# peripheral.net
KiCad netlist of a schematic drawn in Altium Designer
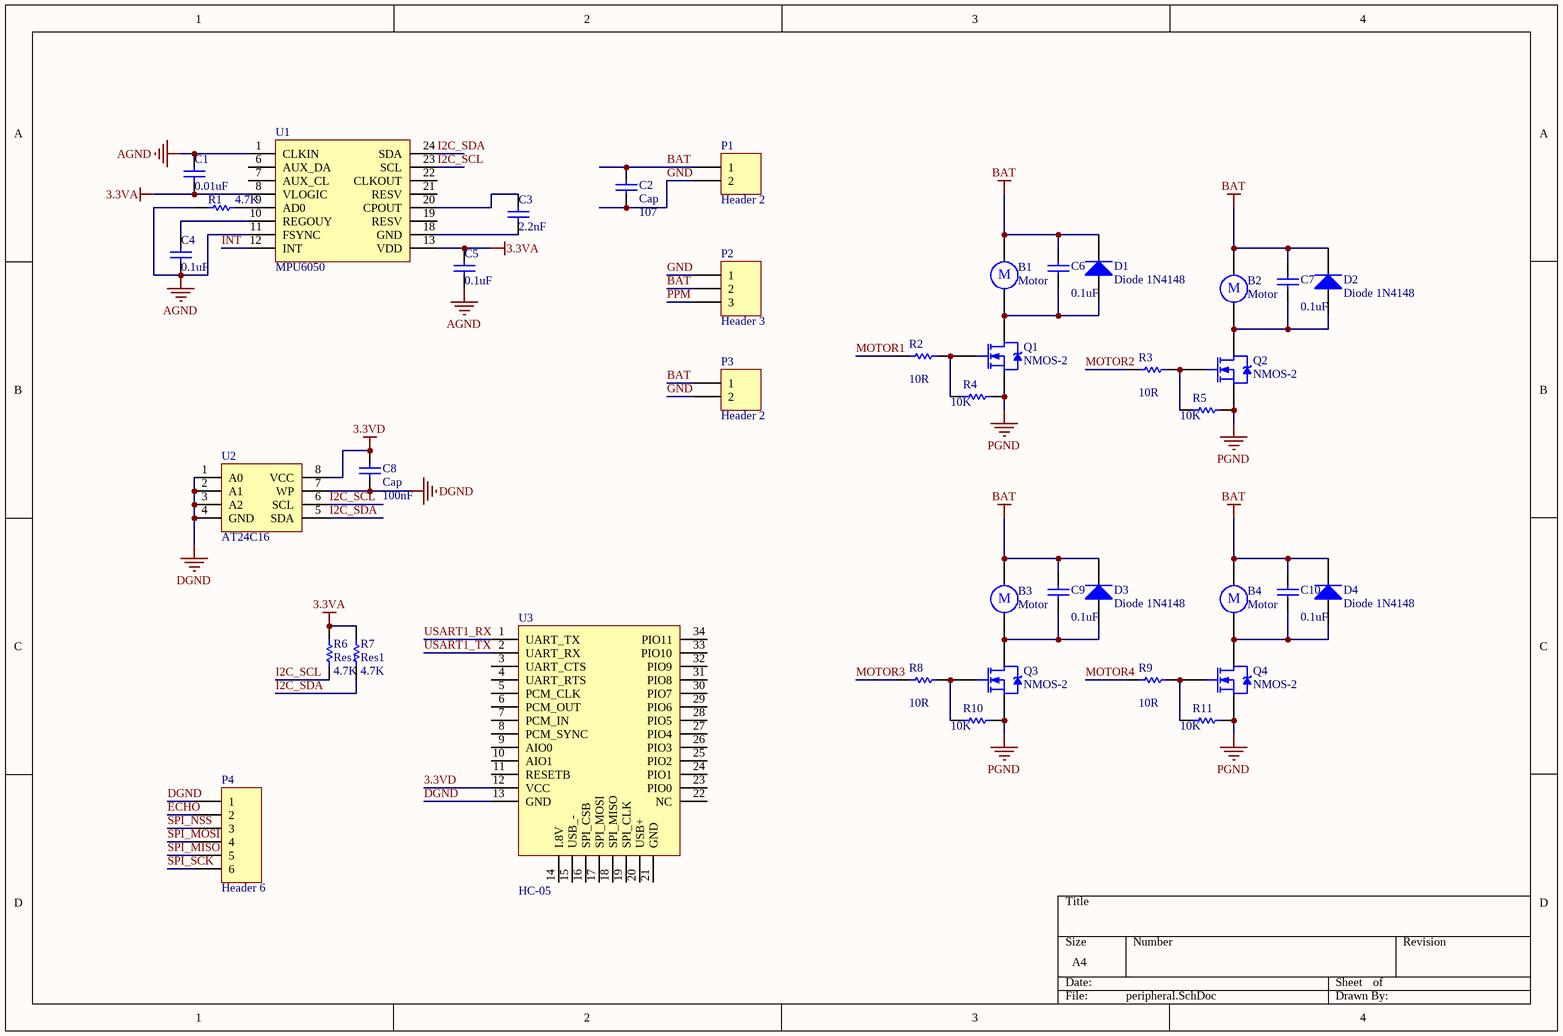
[diagram p0: peripheral.SchDoc]

(export (version "E")
  (design (tool "Eeschema 10.0.6"))
  (components
    (comp (ref "B1")
      (value "Motor")
      (footprint "HDR1X2")
      (description "Motor, General Kind")
      (fields (field (name "PUBLISHER") "Altium Limited"))
      (libsource (lib "Miscellaneous Devices") (part "Motor"))
    )
    (comp (ref "B2")
      (value "Motor")
      (footprint "HDR1X2")
      (description "Motor, General Kind")
      (fields (field (name "PUBLISHER") "Altium Limited"))
      (libsource (lib "Miscellaneous Devices") (part "Motor"))
    )
    (comp (ref "B3")
      (value "Motor")
      (footprint "HDR1X2")
      (description "Motor, General Kind")
      (fields (field (name "PUBLISHER") "Altium Limited"))
      (libsource (lib "Miscellaneous Devices") (part "Motor"))
    )
    (comp (ref "B4")
      (value "Motor")
      (footprint "HDR1X2")
      (description "Motor, General Kind")
      (fields (field (name "PUBLISHER") "Altium Limited"))
      (libsource (lib "Miscellaneous Devices") (part "Motor"))
    )
    (comp (ref "C1")
      (value "0.01uF")
      (footprint "C0402")
      (description "Capacitor")
      (fields (field (name "Comment") "Cap") (field (name "PUBLISHER") "Altium Limited"))
      (libsource (lib "Miscellaneous Devices") (part "Cap"))
    )
    (comp (ref "C2")
      (value "Cap")
      (footprint "1206R")
      (description "Capacitor")
      (fields (field (name "ALTIUM_VALUE") "107") (field (name "PUBLISHER") "Altium Limited"))
      (libsource (lib "Miscellaneous Devices") (part "Cap"))
    )
    (comp (ref "C3")
      (value "2.2nF")
      (footprint "C0402")
      (description "Capacitor")
      (fields (field (name "Comment") "Cap") (field (name "PUBLISHER") "Altium Limited"))
      (libsource (lib "Miscellaneous Devices") (part "Cap"))
    )
    (comp (ref "C4")
      (value "0.1uF")
      (footprint "C0402")
      (description "Capacitor")
      (fields (field (name "Comment") "Cap") (field (name "PUBLISHER") "Altium Limited"))
      (libsource (lib "Miscellaneous Devices") (part "Cap"))
    )
    (comp (ref "C5")
      (value "0.1uF")
      (footprint "C0402")
      (description "Capacitor")
      (fields (field (name "Comment") "Cap") (field (name "PUBLISHER") "Altium Limited"))
      (libsource (lib "Miscellaneous Devices") (part "Cap"))
    )
    (comp (ref "C6")
      (value "0.1uF")
      (footprint "c0603")
      (description "Capacitor")
      (fields (field (name "Comment") "Cap") (field (name "PUBLISHER") "Altium Limited"))
      (libsource (lib "Miscellaneous Devices") (part "Cap"))
    )
    (comp (ref "C7")
      (value "0.1uF")
      (footprint "c0603")
      (description "Capacitor")
      (fields (field (name "Comment") "Cap") (field (name "PUBLISHER") "Altium Limited"))
      (libsource (lib "Miscellaneous Devices") (part "Cap"))
    )
    (comp (ref "C8")
      (value "Cap")
      (footprint "C0402")
      (description "Capacitor")
      (fields (field (name "ALTIUM_VALUE") "100nF") (field (name "PUBLISHER") "Altium Limited"))
      (libsource (lib "Miscellaneous Devices") (part "Cap"))
    )
    (comp (ref "C9")
      (value "0.1uF")
      (footprint "c0603")
      (description "Capacitor")
      (fields (field (name "Comment") "Cap") (field (name "PUBLISHER") "Altium Limited"))
      (libsource (lib "Miscellaneous Devices") (part "Cap"))
    )
    (comp (ref "C10")
      (value "0.1uF")
      (footprint "c0603")
      (description "Capacitor")
      (fields (field (name "Comment") "Cap") (field (name "PUBLISHER") "Altium Limited"))
      (libsource (lib "Miscellaneous Devices") (part "Cap"))
    )
    (comp (ref "D1")
      (value "Diode 1N4148")
      (footprint "SOD-523")
      (description "High Conductance Fast Diode")
      (fields (field (name "PUBLISHER") "Altium Limited"))
      (libsource (lib "Miscellaneous Devices") (part "Diode 1N4148"))
    )
    (comp (ref "D2")
      (value "Diode 1N4148")
      (footprint "SOD-523")
      (description "High Conductance Fast Diode")
      (fields (field (name "PUBLISHER") "Altium Limited"))
      (libsource (lib "Miscellaneous Devices") (part "Diode 1N4148"))
    )
    (comp (ref "D3")
      (value "Diode 1N4148")
      (footprint "SOD-523")
      (description "High Conductance Fast Diode")
      (fields (field (name "PUBLISHER") "Altium Limited"))
      (libsource (lib "Miscellaneous Devices") (part "Diode 1N4148"))
    )
    (comp (ref "D4")
      (value "Diode 1N4148")
      (footprint "SOD-523")
      (description "High Conductance Fast Diode")
      (fields (field (name "PUBLISHER") "Altium Limited"))
      (libsource (lib "Miscellaneous Devices") (part "Diode 1N4148"))
    )
    (comp (ref "P1")
      (value "Header 2")
      (footprint "BATHOLE")
      (description "Header, 2-Pin")
      (fields (field (name "PUBLISHER") "Altium Limited"))
      (libsource (lib "Miscellaneous Connectors") (part "Header 2"))
    )
    (comp (ref "P2")
      (value "Header 3")
      (footprint "HDR1X3")
      (description "Header, 3-Pin")
      (fields (field (name "PUBLISHER") "Altium Limited"))
      (libsource (lib "Miscellaneous Connectors") (part "Header 3"))
    )
    (comp (ref "P3")
      (value "Header 2")
      (footprint "BATHOLE")
      (description "Header, 2-Pin")
      (fields (field (name "PUBLISHER") "Altium Limited"))
      (libsource (lib "Miscellaneous Connectors") (part "Header 2"))
    )
    (comp (ref "P4")
      (value "Header 6")
      (footprint "1.0*6PIN/SMD H")
      (description "Header, 6-Pin")
      (fields (field (name "PUBLISHER") "Altium Limited"))
      (libsource (lib "Miscellaneous Connectors") (part "Header 6"))
    )
    (comp (ref "Q1")
      (value "NMOS-2")
      (footprint "WDFN8 3.3*3.3,0.65P")
      (description "N-Channel Power MOSFET")
      (fields (field (name "PUBLISHER") "Altium Limited"))
      (libsource (lib "四旋翼") (part "NMOS-2"))
    )
    (comp (ref "Q2")
      (value "NMOS-2")
      (footprint "WDFN8 3.3*3.3,0.65P")
      (description "N-Channel Power MOSFET")
      (fields (field (name "PUBLISHER") "Altium Limited"))
      (libsource (lib "四旋翼") (part "NMOS-2"))
    )
    (comp (ref "Q3")
      (value "NMOS-2")
      (footprint "WDFN8 3.3*3.3,0.65P")
      (description "N-Channel Power MOSFET")
      (fields (field (name "PUBLISHER") "Altium Limited"))
      (libsource (lib "四旋翼") (part "NMOS-2"))
    )
    (comp (ref "Q4")
      (value "NMOS-2")
      (footprint "WDFN8 3.3*3.3,0.65P")
      (description "N-Channel Power MOSFET")
      (fields (field (name "PUBLISHER") "Altium Limited"))
      (libsource (lib "四旋翼") (part "NMOS-2"))
    )
    (comp (ref "R1")
      (value "4.7K")
      (footprint "R0402")
      (description "Resistor")
      (fields (field (name "Comment") "Res1") (field (name "PUBLISHER") "Altium Limited"))
      (libsource (lib "Miscellaneous Devices") (part "Res1"))
    )
    (comp (ref "R2")
      (value "10R")
      (footprint "R0402")
      (description "Resistor")
      (fields (field (name "Comment") "Res1") (field (name "PUBLISHER") "Altium Limited"))
      (libsource (lib "Miscellaneous Devices") (part "Res1"))
    )
    (comp (ref "R3")
      (value "10R")
      (footprint "R0402")
      (description "Resistor")
      (fields (field (name "Comment") "Res1") (field (name "PUBLISHER") "Altium Limited"))
      (libsource (lib "Miscellaneous Devices") (part "Res1"))
    )
    (comp (ref "R4")
      (value "10K")
      (footprint "R0402")
      (description "Resistor")
      (fields (field (name "Comment") "Res1") (field (name "PUBLISHER") "Altium Limited"))
      (libsource (lib "Miscellaneous Devices") (part "Res1"))
    )
    (comp (ref "R5")
      (value "10K")
      (footprint "R0402")
      (description "Resistor")
      (fields (field (name "Comment") "Res1") (field (name "PUBLISHER") "Altium Limited"))
      (libsource (lib "Miscellaneous Devices") (part "Res1"))
    )
    (comp (ref "R6")
      (value "Res1")
      (footprint "R0402")
      (description "Resistor")
      (fields (field (name "ALTIUM_VALUE") "4.7K") (field (name "PUBLISHER") "Altium Limited"))
      (libsource (lib "Miscellaneous Devices") (part "Res1"))
    )
    (comp (ref "R7")
      (value "Res1")
      (footprint "R0402")
      (description "Resistor")
      (fields (field (name "ALTIUM_VALUE") "4.7K") (field (name "PUBLISHER") "Altium Limited"))
      (libsource (lib "Miscellaneous Devices") (part "Res1"))
    )
    (comp (ref "R8")
      (value "10R")
      (footprint "R0402")
      (description "Resistor")
      (fields (field (name "Comment") "Res1") (field (name "PUBLISHER") "Altium Limited"))
      (libsource (lib "Miscellaneous Devices") (part "Res1"))
    )
    (comp (ref "R9")
      (value "10R")
      (footprint "R0402")
      (description "Resistor")
      (fields (field (name "Comment") "Res1") (field (name "PUBLISHER") "Altium Limited"))
      (libsource (lib "Miscellaneous Devices") (part "Res1"))
    )
    (comp (ref "R10")
      (value "10K")
      (footprint "R0402")
      (description "Resistor")
      (fields (field (name "Comment") "Res1") (field (name "PUBLISHER") "Altium Limited"))
      (libsource (lib "Miscellaneous Devices") (part "Res1"))
    )
    (comp (ref "R11")
      (value "10K")
      (footprint "R0402")
      (description "Resistor")
      (fields (field (name "Comment") "Res1") (field (name "PUBLISHER") "Altium Limited"))
      (libsource (lib "Miscellaneous Devices") (part "Res1"))
    )
    (comp (ref "U1") (value "MPU6050") (footprint "QFN24") (libsource (lib "四旋翼") (part "MPU6050")))
    (comp (ref "U2") (value "AT24C16") (footprint "TSSOP8") (libsource (lib "四旋翼") (part "AT24C16")))
    (comp (ref "U3") (value "HC-05") (footprint "hc05") (libsource (lib "四旋翼") (part "HC05")))
  )
  (nets
    (net (code "1") (name "/ECHO") (class "Default")
      (node (ref "P4") (pin "2") (pinfunction "2_2") (pintype "passive"))
    )
    (net (code "2") (name "/GND") (class "Default")
      (node (ref "C2") (pin "1") (pinfunction "1_1") (pintype "passive"))
      (node (ref "P1") (pin "2") (pinfunction "2_2") (pintype "passive"))
      (node (ref "P2") (pin "1") (pinfunction "1_1") (pintype "passive"))
      (node (ref "P3") (pin "2") (pinfunction "2_2") (pintype "passive"))
    )
    (net (code "3") (name "/I2C_SCL") (class "Default")
      (node (ref "R6") (pin "1") (pinfunction "1_1") (pintype "passive"))
      (node (ref "U1") (pin "23") (pinfunction "SCL_23") (pintype "passive"))
      (node (ref "U2") (pin "6") (pinfunction "SCL_6") (pintype "passive"))
    )
    (net (code "4") (name "/I2C_SDA") (class "Default")
      (node (ref "R7") (pin "1") (pinfunction "1_1") (pintype "passive"))
      (node (ref "U1") (pin "24") (pinfunction "SDA_24") (pintype "passive"))
      (node (ref "U2") (pin "5") (pinfunction "SDA_5") (pintype "passive"))
    )
    (net (code "5") (name "/INT") (class "Default")
      (node (ref "U1") (pin "12") (pinfunction "INT_12") (pintype "passive"))
    )
    (net (code "6") (name "/MOTOR1") (class "Default")
      (node (ref "R2") (pin "1") (pinfunction "1_1") (pintype "passive"))
    )
    (net (code "7") (name "/MOTOR2") (class "Default")
      (node (ref "R3") (pin "1") (pinfunction "1_1") (pintype "passive"))
    )
    (net (code "8") (name "/MOTOR3") (class "Default")
      (node (ref "R8") (pin "1") (pinfunction "1_1") (pintype "passive"))
    )
    (net (code "9") (name "/MOTOR4") (class "Default")
      (node (ref "R9") (pin "1") (pinfunction "1_1") (pintype "passive"))
    )
    (net (code "10") (name "/PPM") (class "Default")
      (node (ref "P2") (pin "3") (pinfunction "3_3") (pintype "passive"))
    )
    (net (code "11") (name "/SPI_MISO") (class "Default")
      (node (ref "P4") (pin "5") (pinfunction "5_5") (pintype "passive"))
    )
    (net (code "12") (name "/SPI_MOSI") (class "Default")
      (node (ref "P4") (pin "4") (pinfunction "4_4") (pintype "passive"))
    )
    (net (code "13") (name "/SPI_NSS") (class "Default")
      (node (ref "P4") (pin "3") (pinfunction "3_3") (pintype "passive"))
    )
    (net (code "14") (name "/SPI_SCK") (class "Default")
      (node (ref "P4") (pin "6") (pinfunction "6_6") (pintype "passive"))
    )
    (net (code "15") (name "/USART1_RX") (class "Default")
      (node (ref "U3") (pin "1") (pinfunction "UART_TX_1") (pintype "passive"))
    )
    (net (code "16") (name "/USART1_TX") (class "Default")
      (node (ref "U3") (pin "2") (pinfunction "UART_RX_2") (pintype "passive"))
    )
    (net (code "17") (name "3.3VA") (class "Default")
      (node (ref "C1") (pin "1") (pinfunction "1_1") (pintype "passive"))
      (node (ref "C5") (pin "2") (pinfunction "2_2") (pintype "passive"))
      (node (ref "R6") (pin "2") (pinfunction "2_2") (pintype "passive"))
      (node (ref "R7") (pin "2") (pinfunction "2_2") (pintype "passive"))
      (node (ref "U1") (pin "13") (pinfunction "VDD_13") (pintype "passive"))
      (node (ref "U1") (pin "8") (pinfunction "VLOGIC_8") (pintype "passive"))
    )
    (net (code "18") (name "3.3VD") (class "Default")
      (node (ref "C8") (pin "2") (pinfunction "2_2") (pintype "passive"))
      (node (ref "U2") (pin "8") (pinfunction "VCC_8") (pintype "passive"))
      (node (ref "U3") (pin "12") (pinfunction "VCC_12") (pintype "passive"))
    )
    (net (code "19") (name "AGND") (class "Default")
      (node (ref "C1") (pin "2") (pinfunction "2_2") (pintype "passive"))
      (node (ref "C4") (pin "1") (pinfunction "1_1") (pintype "passive"))
      (node (ref "C5") (pin "1") (pinfunction "1_1") (pintype "passive"))
      (node (ref "R1") (pin "2") (pinfunction "2_2") (pintype "passive"))
      (node (ref "U1") (pin "1") (pinfunction "CLKIN_1") (pintype "passive"))
      (node (ref "U1") (pin "11") (pinfunction "FSYNC_11") (pintype "passive"))
    )
    (net (code "20") (name "BAT") (class "Default")
      (node (ref "B1") (pin "1") (pinfunction "1_1") (pintype "passive"))
      (node (ref "B2") (pin "1") (pinfunction "1_1") (pintype "passive"))
      (node (ref "B3") (pin "1") (pinfunction "1_1") (pintype "passive"))
      (node (ref "B4") (pin "1") (pinfunction "1_1") (pintype "passive"))
      (node (ref "C10") (pin "2") (pinfunction "2_2") (pintype "passive"))
      (node (ref "C2") (pin "2") (pinfunction "2_2") (pintype "passive"))
      (node (ref "C6") (pin "2") (pinfunction "2_2") (pintype "passive"))
      (node (ref "C7") (pin "2") (pinfunction "2_2") (pintype "passive"))
      (node (ref "C9") (pin "2") (pinfunction "2_2") (pintype "passive"))
      (node (ref "D1") (pin "2") (pinfunction "K_2") (pintype "passive"))
      (node (ref "D2") (pin "2") (pinfunction "K_2") (pintype "passive"))
      (node (ref "D3") (pin "2") (pinfunction "K_2") (pintype "passive"))
      (node (ref "D4") (pin "2") (pinfunction "K_2") (pintype "passive"))
      (node (ref "P1") (pin "1") (pinfunction "1_1") (pintype "passive"))
      (node (ref "P2") (pin "2") (pinfunction "2_2") (pintype "passive"))
      (node (ref "P3") (pin "1") (pinfunction "1_1") (pintype "passive"))
    )
    (net (code "21") (name "DGND") (class "Default")
      (node (ref "C8") (pin "1") (pinfunction "1_1") (pintype "passive"))
      (node (ref "P4") (pin "1") (pinfunction "1_1") (pintype "passive"))
      (node (ref "U2") (pin "1") (pinfunction "A0_1") (pintype "passive"))
      (node (ref "U2") (pin "2") (pinfunction "A1_2") (pintype "passive"))
      (node (ref "U2") (pin "3") (pinfunction "A2_3") (pintype "passive"))
      (node (ref "U2") (pin "4") (pinfunction "GND_4") (pintype "passive"))
      (node (ref "U2") (pin "7") (pinfunction "WP_7") (pintype "passive"))
      (node (ref "U3") (pin "13") (pinfunction "GND_13") (pintype "passive"))
    )
    (net (code "22") (name "Net-(D1-A)") (class "Default")
      (node (ref "B1") (pin "2") (pinfunction "2_2") (pintype "passive"))
      (node (ref "C6") (pin "1") (pinfunction "1_1") (pintype "passive"))
      (node (ref "D1") (pin "1") (pinfunction "A_1") (pintype "passive"))
      (node (ref "Q1") (pin "3") (pinfunction "D_3") (pintype "passive"))
    )
    (net (code "23") (name "Net-(D2-A)") (class "Default")
      (node (ref "B2") (pin "2") (pinfunction "2_2") (pintype "passive"))
      (node (ref "C7") (pin "1") (pinfunction "1_1") (pintype "passive"))
      (node (ref "D2") (pin "1") (pinfunction "A_1") (pintype "passive"))
      (node (ref "Q2") (pin "3") (pinfunction "D_3") (pintype "passive"))
    )
    (net (code "24") (name "Net-(D3-A)") (class "Default")
      (node (ref "B3") (pin "2") (pinfunction "2_2") (pintype "passive"))
      (node (ref "C9") (pin "1") (pinfunction "1_1") (pintype "passive"))
      (node (ref "D3") (pin "1") (pinfunction "A_1") (pintype "passive"))
      (node (ref "Q3") (pin "3") (pinfunction "D_3") (pintype "passive"))
    )
    (net (code "25") (name "Net-(D4-A)") (class "Default")
      (node (ref "B4") (pin "2") (pinfunction "2_2") (pintype "passive"))
      (node (ref "C10") (pin "1") (pinfunction "1_1") (pintype "passive"))
      (node (ref "D4") (pin "1") (pinfunction "A_1") (pintype "passive"))
      (node (ref "Q4") (pin "3") (pinfunction "D_3") (pintype "passive"))
    )
    (net (code "26") (name "Net-(Q1-G)") (class "Default")
      (node (ref "Q1") (pin "1") (pinfunction "G_1") (pintype "passive"))
      (node (ref "R2") (pin "2") (pinfunction "2_2") (pintype "passive"))
      (node (ref "R4") (pin "1") (pinfunction "1_1") (pintype "passive"))
    )
    (net (code "27") (name "Net-(Q2-G)") (class "Default")
      (node (ref "Q2") (pin "1") (pinfunction "G_1") (pintype "passive"))
      (node (ref "R3") (pin "2") (pinfunction "2_2") (pintype "passive"))
      (node (ref "R5") (pin "1") (pinfunction "1_1") (pintype "passive"))
    )
    (net (code "28") (name "Net-(Q3-G)") (class "Default")
      (node (ref "Q3") (pin "1") (pinfunction "G_1") (pintype "passive"))
      (node (ref "R10") (pin "1") (pinfunction "1_1") (pintype "passive"))
      (node (ref "R8") (pin "2") (pinfunction "2_2") (pintype "passive"))
    )
    (net (code "29") (name "Net-(Q4-G)") (class "Default")
      (node (ref "Q4") (pin "1") (pinfunction "G_1") (pintype "passive"))
      (node (ref "R11") (pin "1") (pinfunction "1_1") (pintype "passive"))
      (node (ref "R9") (pin "2") (pinfunction "2_2") (pintype "passive"))
    )
    (net (code "30") (name "Net-(U1-AD0)") (class "Default")
      (node (ref "R1") (pin "1") (pinfunction "1_1") (pintype "passive"))
      (node (ref "U1") (pin "9") (pinfunction "AD0_9") (pintype "passive"))
    )
    (net (code "31") (name "Net-(U1-CPOUT)") (class "Default")
      (node (ref "C3") (pin "2") (pinfunction "2_2") (pintype "passive"))
      (node (ref "U1") (pin "20") (pinfunction "CPOUT_20") (pintype "passive"))
    )
    (net (code "32") (name "Net-(U1-GND)") (class "Default")
      (node (ref "C3") (pin "1") (pinfunction "1_1") (pintype "passive"))
      (node (ref "U1") (pin "18") (pinfunction "GND_18") (pintype "passive"))
    )
    (net (code "33") (name "Net-(U1-REGOUY)") (class "Default")
      (node (ref "C4") (pin "2") (pinfunction "2_2") (pintype "passive"))
      (node (ref "U1") (pin "10") (pinfunction "REGOUY_10") (pintype "passive"))
    )
    (net (code "34") (name "PGND") (class "Default")
      (node (ref "Q1") (pin "2") (pinfunction "S_2") (pintype "passive"))
      (node (ref "Q2") (pin "2") (pinfunction "S_2") (pintype "passive"))
      (node (ref "Q3") (pin "2") (pinfunction "S_2") (pintype "passive"))
      (node (ref "Q4") (pin "2") (pinfunction "S_2") (pintype "passive"))
      (node (ref "R10") (pin "2") (pinfunction "2_2") (pintype "passive"))
      (node (ref "R11") (pin "2") (pinfunction "2_2") (pintype "passive"))
      (node (ref "R4") (pin "2") (pinfunction "2_2") (pintype "passive"))
      (node (ref "R5") (pin "2") (pinfunction "2_2") (pintype "passive"))
    )
    (net (code "35") (name "unconnected-(U1-AUX_CL-Pad7)") (class "Default")
      (node (ref "U1") (pin "7") (pinfunction "AUX_CL_7") (pintype "passive"))
    )
    (net (code "36") (name "unconnected-(U1-AUX_DA-Pad6)") (class "Default")
      (node (ref "U1") (pin "6") (pinfunction "AUX_DA_6") (pintype "passive"))
    )
    (net (code "37") (name "unconnected-(U1-CLKOUT-Pad22)") (class "Default")
      (node (ref "U1") (pin "22") (pinfunction "CLKOUT_22") (pintype "passive"))
    )
    (net (code "38") (name "unconnected-(U1-RESV-Pad19)") (class "Default")
      (node (ref "U1") (pin "19") (pinfunction "RESV_19") (pintype "passive"))
    )
    (net (code "39") (name "unconnected-(U1-RESV-Pad21)") (class "Default")
      (node (ref "U1") (pin "21") (pinfunction "RESV_21") (pintype "passive"))
    )
    (net (code "40") (name "unconnected-(U3-AIO0-Pad9)") (class "Default")
      (node (ref "U3") (pin "9") (pinfunction "AIO0_9") (pintype "passive"))
    )
    (net (code "41") (name "unconnected-(U3-AIO1-Pad10)") (class "Default")
      (node (ref "U3") (pin "10") (pinfunction "AIO1_10") (pintype "passive"))
    )
    (net (code "42") (name "unconnected-(U3-GND-Pad21)") (class "Default")
      (node (ref "U3") (pin "21") (pinfunction "GND_21") (pintype "passive"))
    )
    (net (code "43") (name "unconnected-(U3-I.8V-Pad14)") (class "Default")
      (node (ref "U3") (pin "14") (pinfunction "I.8V_14") (pintype "passive"))
    )
    (net (code "44") (name "unconnected-(U3-NC-Pad22)") (class "Default")
      (node (ref "U3") (pin "22") (pinfunction "NC_22") (pintype "passive"))
    )
    (net (code "45") (name "unconnected-(U3-PCM_CLK-Pad5)") (class "Default")
      (node (ref "U3") (pin "5") (pinfunction "PCM_CLK_5") (pintype "passive"))
    )
    (net (code "46") (name "unconnected-(U3-PCM_IN-Pad7)") (class "Default")
      (node (ref "U3") (pin "7") (pinfunction "PCM_IN_7") (pintype "passive"))
    )
    (net (code "47") (name "unconnected-(U3-PCM_OUT-Pad6)") (class "Default")
      (node (ref "U3") (pin "6") (pinfunction "PCM_OUT_6") (pintype "passive"))
    )
    (net (code "48") (name "unconnected-(U3-PCM_SYNC-Pad8)") (class "Default")
      (node (ref "U3") (pin "8") (pinfunction "PCM_SYNC_8") (pintype "passive"))
    )
    (net (code "49") (name "unconnected-(U3-PIO0-Pad23)") (class "Default")
      (node (ref "U3") (pin "23") (pinfunction "PIO0_23") (pintype "passive"))
    )
    (net (code "50") (name "unconnected-(U3-PIO1-Pad24)") (class "Default")
      (node (ref "U3") (pin "24") (pinfunction "PIO1_24") (pintype "passive"))
    )
    (net (code "51") (name "unconnected-(U3-PIO2-Pad25)") (class "Default")
      (node (ref "U3") (pin "25") (pinfunction "PIO2_25") (pintype "passive"))
    )
    (net (code "52") (name "unconnected-(U3-PIO3-Pad26)") (class "Default")
      (node (ref "U3") (pin "26") (pinfunction "PIO3_26") (pintype "passive"))
    )
    (net (code "53") (name "unconnected-(U3-PIO4-Pad27)") (class "Default")
      (node (ref "U3") (pin "27") (pinfunction "PIO4_27") (pintype "passive"))
    )
    (net (code "54") (name "unconnected-(U3-PIO5-Pad28)") (class "Default")
      (node (ref "U3") (pin "28") (pinfunction "PIO5_28") (pintype "passive"))
    )
    (net (code "55") (name "unconnected-(U3-PIO6-Pad29)") (class "Default")
      (node (ref "U3") (pin "29") (pinfunction "PIO6_29") (pintype "passive"))
    )
    (net (code "56") (name "unconnected-(U3-PIO7-Pad30)") (class "Default")
      (node (ref "U3") (pin "30") (pinfunction "PIO7_30") (pintype "passive"))
    )
    (net (code "57") (name "unconnected-(U3-PIO8-Pad31)") (class "Default")
      (node (ref "U3") (pin "31") (pinfunction "PIO8_31") (pintype "passive"))
    )
    (net (code "58") (name "unconnected-(U3-PIO9-Pad32)") (class "Default")
      (node (ref "U3") (pin "32") (pinfunction "PIO9_32") (pintype "passive"))
    )
    (net (code "59") (name "unconnected-(U3-PIO10-Pad33)") (class "Default")
      (node (ref "U3") (pin "33") (pinfunction "PIO10_33") (pintype "passive"))
    )
    (net (code "60") (name "unconnected-(U3-PIO11-Pad34)") (class "Default")
      (node (ref "U3") (pin "34") (pinfunction "PIO11_34") (pintype "passive"))
    )
    (net (code "61") (name "unconnected-(U3-RESETB-Pad11)") (class "Default")
      (node (ref "U3") (pin "11") (pinfunction "RESETB_11") (pintype "passive"))
    )
    (net (code "62") (name "unconnected-(U3-SPI_CLK-Pad19)") (class "Default")
      (node (ref "U3") (pin "19") (pinfunction "SPI_CLK_19") (pintype "passive"))
    )
    (net (code "63") (name "unconnected-(U3-SPI_CSB-Pad16)") (class "Default")
      (node (ref "U3") (pin "16") (pinfunction "SPI_CSB_16") (pintype "passive"))
    )
    (net (code "64") (name "unconnected-(U3-SPI_MISO-Pad18)") (class "Default")
      (node (ref "U3") (pin "18") (pinfunction "SPI_MISO_18") (pintype "passive"))
    )
    (net (code "65") (name "unconnected-(U3-SPI_MOSI-Pad17)") (class "Default")
      (node (ref "U3") (pin "17") (pinfunction "SPI_MOSI_17") (pintype "passive"))
    )
    (net (code "66") (name "unconnected-(U3-UART_CTS-Pad3)") (class "Default")
      (node (ref "U3") (pin "3") (pinfunction "UART_CTS_3") (pintype "passive"))
    )
    (net (code "67") (name "unconnected-(U3-UART_RTS-Pad4)") (class "Default")
      (node (ref "U3") (pin "4") (pinfunction "UART_RTS_4") (pintype "passive"))
    )
    (net (code "68") (name "unconnected-(U3-USB+-Pad20)") (class "Default")
      (node (ref "U3") (pin "20") (pinfunction "USB+_20") (pintype "passive"))
    )
    (net (code "69") (name "unconnected-(U3-USB_--Pad15)") (class "Default")
      (node (ref "U3") (pin "15") (pinfunction "USB_-_15") (pintype "passive"))
    )
  )
)
